# MMC_Interface.net
KiCad netlist of a schematic drawn in Altium Designer
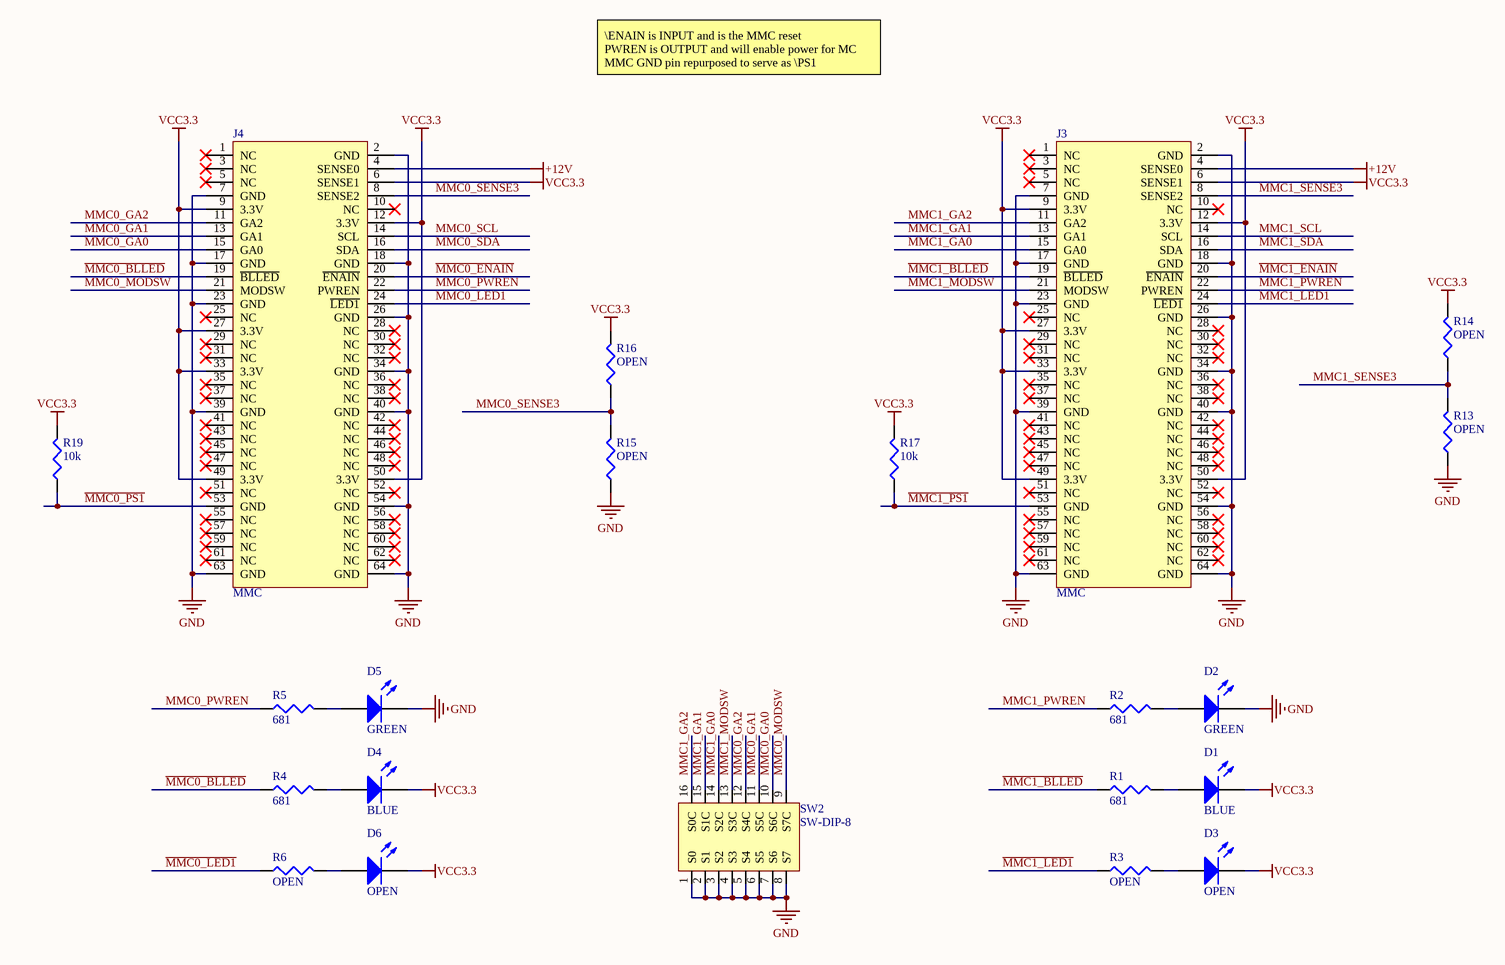
[diagram p0: MMC_Interface.SchDoc]

(export (version "E")
  (design (tool "Eeschema 10.0.6"))
  (components
    (comp (ref "D1")
      (value "BLUE")
      (footprint "LED0603_M")
      (description "Light Emitting Diode")
      (fields (field (name "MFG. PART NO.") "LTST-S270TBKT"))
      (libsource (lib "CustomSymbols") (part "LED"))
    )
    (comp (ref "D2")
      (value "GREEN")
      (footprint "LED0603_M")
      (description "Light Emitting Diode")
      (fields (field (name "MFG. PART NO.") "LTST-S270KGKT"))
      (libsource (lib "CustomSymbols") (part "LED"))
    )
    (comp (ref "D3")
      (value "OPEN")
      (footprint "LED0603_M")
      (description "Light Emitting Diode")
      (fields (field (name "MFG. PART NO.") "NA"))
      (libsource (lib "CustomSymbols") (part "LED"))
    )
    (comp (ref "D4")
      (value "BLUE")
      (footprint "LED0603_M")
      (description "Light Emitting Diode")
      (fields (field (name "MFG. PART NO.") "LTST-S270TBKT"))
      (libsource (lib "CustomSymbols") (part "LED"))
    )
    (comp (ref "D5")
      (value "GREEN")
      (footprint "LED0603_M")
      (description "Light Emitting Diode")
      (fields (field (name "MFG. PART NO.") "LTST-S270KGKT"))
      (libsource (lib "CustomSymbols") (part "LED"))
    )
    (comp (ref "D6")
      (value "OPEN")
      (footprint "LED0603_M")
      (description "Light Emitting Diode")
      (fields (field (name "MFG. PART NO.") "NA"))
      (libsource (lib "CustomSymbols") (part "LED"))
    )
    (comp (ref "J3")
      (value "MMC")
      (footprint "5120527-1")
      (description "TE 5120527-1")
      (fields (field (name "MFG. PART NO.") "5120527-1"))
      (libsource (lib "CustomSymbols") (part "MMC"))
    )
    (comp (ref "J4")
      (value "MMC")
      (footprint "5120527-1")
      (description "TE 5120527-1")
      (fields (field (name "MFG. PART NO.") "5120527-1"))
      (libsource (lib "CustomSymbols") (part "MMC"))
    )
    (comp (ref "R1")
      (value "681")
      (footprint "R0603")
      (description "Resistor")
      (fields (field (name "TOLERANCE") "1%") (field (name "MFG. PART NO.") "RC0603FR-07681RL"))
      (libsource (lib "CustomSymbols") (part "Res"))
    )
    (comp (ref "R2")
      (value "681")
      (footprint "R0603")
      (description "Resistor")
      (fields (field (name "TOLERANCE") "1%") (field (name "MFG. PART NO.") "RC0603FR-07681RL"))
      (libsource (lib "CustomSymbols") (part "Res"))
    )
    (comp (ref "R3")
      (value "OPEN")
      (footprint "R0402_IPC_H")
      (description "Resistor")
      (fields (field (name "TOLERANCE") "1%") (field (name "MFG. PART NO.") "NA"))
      (libsource (lib "CustomSymbols") (part "Res"))
    )
    (comp (ref "R4")
      (value "681")
      (footprint "R0603")
      (description "Resistor")
      (fields (field (name "TOLERANCE") "1%") (field (name "MFG. PART NO.") "RC0603FR-07681RL"))
      (libsource (lib "CustomSymbols") (part "Res"))
    )
    (comp (ref "R5")
      (value "681")
      (footprint "R0603")
      (description "Resistor")
      (fields (field (name "TOLERANCE") "1%") (field (name "MFG. PART NO.") "RC0603FR-07681RL"))
      (libsource (lib "CustomSymbols") (part "Res"))
    )
    (comp (ref "R6")
      (value "OPEN")
      (footprint "R0402_IPC_H")
      (description "Resistor")
      (fields (field (name "TOLERANCE") "1%") (field (name "MFG. PART NO.") "NA"))
      (libsource (lib "CustomSymbols") (part "Res"))
    )
    (comp (ref "R13")
      (value "OPEN")
      (footprint "R0402_IPC_H")
      (description "Resistor")
      (fields (field (name "TOLERANCE") "1%") (field (name "MFG. PART NO.") "NA"))
      (libsource (lib "CustomSymbols") (part "Res"))
    )
    (comp (ref "R14")
      (value "OPEN")
      (footprint "R0402_IPC_H")
      (description "Resistor")
      (fields (field (name "TOLERANCE") "1%") (field (name "MFG. PART NO.") "NA"))
      (libsource (lib "CustomSymbols") (part "Res"))
    )
    (comp (ref "R15")
      (value "OPEN")
      (footprint "R0402_IPC_H")
      (description "Resistor")
      (fields (field (name "TOLERANCE") "1%") (field (name "MFG. PART NO.") "NA"))
      (libsource (lib "CustomSymbols") (part "Res"))
    )
    (comp (ref "R16")
      (value "OPEN")
      (footprint "R0402_IPC_H")
      (description "Resistor")
      (fields (field (name "TOLERANCE") "1%") (field (name "MFG. PART NO.") "NA"))
      (libsource (lib "CustomSymbols") (part "Res"))
    )
    (comp (ref "R17")
      (value "10k")
      (footprint "R0402_IPC_H")
      (description "Resistor")
      (fields (field (name "TOLERANCE") "5%") (field (name "MFG. PART NO.") "ERJ-2GEJ103X"))
      (libsource (lib "CustomSymbols") (part "Res"))
    )
    (comp (ref "R19")
      (value "10k")
      (footprint "R0402_IPC_H")
      (description "Resistor")
      (fields (field (name "TOLERANCE") "5%") (field (name "MFG. PART NO.") "ERJ-2GEJ103X"))
      (libsource (lib "CustomSymbols") (part "Res"))
    )
    (comp (ref "SW2")
      (value "SW-DIP-8")
      (footprint "TDA08H0")
      (description "C&K TDA08H0SB1R")
      (fields (field (name "MFG. PART NO.") "TDA08HOSB1"))
      (libsource (lib "CustomSymbols") (part "SW-DIP-8"))
    )
  )
  (nets
    (net (code "1") (name "+12V") (class "Default")
      (node (ref "J3") (pin "4") (pinfunction "SENSE0_4") (pintype "passive"))
      (node (ref "J4") (pin "4") (pinfunction "SENSE0_4") (pintype "passive"))
    )
    (net (code "2") (name "/MMC0_BLLED") (class "Default")
      (node (ref "J4") (pin "19") (pinfunction "BLLED_19") (pintype "passive"))
      (node (ref "R4") (pin "1") (pinfunction "1_1") (pintype "passive"))
    )
    (net (code "3") (name "/MMC0_ENAIN") (class "Default")
      (node (ref "J4") (pin "20") (pinfunction "ENAIN_20") (pintype "passive"))
    )
    (net (code "4") (name "/MMC0_GA0") (class "Default")
      (node (ref "J4") (pin "15") (pinfunction "GA0_15") (pintype "passive"))
      (node (ref "SW2") (pin "10") (pinfunction "S6C_10") (pintype "passive"))
    )
    (net (code "5") (name "/MMC0_GA1") (class "Default")
      (node (ref "J4") (pin "13") (pinfunction "GA1_13") (pintype "passive"))
      (node (ref "SW2") (pin "11") (pinfunction "S5C_11") (pintype "passive"))
    )
    (net (code "6") (name "/MMC0_GA2") (class "Default")
      (node (ref "J4") (pin "11") (pinfunction "GA2_11") (pintype "passive"))
      (node (ref "SW2") (pin "12") (pinfunction "S4C_12") (pintype "passive"))
    )
    (net (code "7") (name "/MMC0_LED1") (class "Default")
      (node (ref "J4") (pin "24") (pinfunction "LED1_24") (pintype "passive"))
      (node (ref "R6") (pin "1") (pinfunction "1_1") (pintype "passive"))
    )
    (net (code "8") (name "/MMC0_MODSW") (class "Default")
      (node (ref "J4") (pin "21") (pinfunction "MODSW_21") (pintype "passive"))
      (node (ref "SW2") (pin "9") (pinfunction "S7C_9") (pintype "passive"))
    )
    (net (code "9") (name "/MMC0_PS1") (class "Default")
      (node (ref "J4") (pin "53") (pinfunction "GND_53") (pintype "power_in"))
      (node (ref "R19") (pin "1") (pinfunction "1_1") (pintype "passive"))
    )
    (net (code "10") (name "/MMC0_PWREN") (class "Default")
      (node (ref "J4") (pin "22") (pinfunction "PWREN_22") (pintype "passive"))
      (node (ref "R5") (pin "1") (pinfunction "1_1") (pintype "passive"))
    )
    (net (code "11") (name "/MMC0_SCL") (class "Default")
      (node (ref "J4") (pin "14") (pinfunction "SCL_14") (pintype "passive"))
    )
    (net (code "12") (name "/MMC0_SDA") (class "Default")
      (node (ref "J4") (pin "16") (pinfunction "SDA_16") (pintype "passive"))
    )
    (net (code "13") (name "/MMC0_SENSE3") (class "Default")
      (node (ref "J4") (pin "8") (pinfunction "SENSE2_8") (pintype "passive"))
      (node (ref "R15") (pin "2") (pinfunction "2_2") (pintype "passive"))
      (node (ref "R16") (pin "1") (pinfunction "1_1") (pintype "passive"))
    )
    (net (code "14") (name "/MMC1_BLLED") (class "Default")
      (node (ref "J3") (pin "19") (pinfunction "BLLED_19") (pintype "passive"))
      (node (ref "R1") (pin "1") (pinfunction "1_1") (pintype "passive"))
    )
    (net (code "15") (name "/MMC1_ENAIN") (class "Default")
      (node (ref "J3") (pin "20") (pinfunction "ENAIN_20") (pintype "passive"))
    )
    (net (code "16") (name "/MMC1_GA0") (class "Default")
      (node (ref "J3") (pin "15") (pinfunction "GA0_15") (pintype "passive"))
      (node (ref "SW2") (pin "14") (pinfunction "S2C_14") (pintype "passive"))
    )
    (net (code "17") (name "/MMC1_GA1") (class "Default")
      (node (ref "J3") (pin "13") (pinfunction "GA1_13") (pintype "passive"))
      (node (ref "SW2") (pin "15") (pinfunction "S1C_15") (pintype "passive"))
    )
    (net (code "18") (name "/MMC1_GA2") (class "Default")
      (node (ref "J3") (pin "11") (pinfunction "GA2_11") (pintype "passive"))
      (node (ref "SW2") (pin "16") (pinfunction "S0C_16") (pintype "passive"))
    )
    (net (code "19") (name "/MMC1_LED1") (class "Default")
      (node (ref "J3") (pin "24") (pinfunction "LED1_24") (pintype "passive"))
      (node (ref "R3") (pin "1") (pinfunction "1_1") (pintype "passive"))
    )
    (net (code "20") (name "/MMC1_MODSW") (class "Default")
      (node (ref "J3") (pin "21") (pinfunction "MODSW_21") (pintype "passive"))
      (node (ref "SW2") (pin "13") (pinfunction "S3C_13") (pintype "passive"))
    )
    (net (code "21") (name "/MMC1_PS1") (class "Default")
      (node (ref "J3") (pin "53") (pinfunction "GND_53") (pintype "power_in"))
      (node (ref "R17") (pin "1") (pinfunction "1_1") (pintype "passive"))
    )
    (net (code "22") (name "/MMC1_PWREN") (class "Default")
      (node (ref "J3") (pin "22") (pinfunction "PWREN_22") (pintype "passive"))
      (node (ref "R2") (pin "1") (pinfunction "1_1") (pintype "passive"))
    )
    (net (code "23") (name "/MMC1_SCL") (class "Default")
      (node (ref "J3") (pin "14") (pinfunction "SCL_14") (pintype "passive"))
    )
    (net (code "24") (name "/MMC1_SDA") (class "Default")
      (node (ref "J3") (pin "16") (pinfunction "SDA_16") (pintype "passive"))
    )
    (net (code "25") (name "/MMC1_SENSE3") (class "Default")
      (node (ref "J3") (pin "8") (pinfunction "SENSE2_8") (pintype "passive"))
      (node (ref "R13") (pin "2") (pinfunction "2_2") (pintype "passive"))
      (node (ref "R14") (pin "1") (pinfunction "1_1") (pintype "passive"))
    )
    (net (code "26") (name "GND") (class "Default")
      (node (ref "D2") (pin "2") (pinfunction "K_2") (pintype "passive"))
      (node (ref "D5") (pin "2") (pinfunction "K_2") (pintype "passive"))
      (node (ref "J3") (pin "17") (pinfunction "GND_17") (pintype "power_in"))
      (node (ref "J3") (pin "18") (pinfunction "GND_18") (pintype "power_in"))
      (node (ref "J3") (pin "2") (pinfunction "GND_2") (pintype "power_in"))
      (node (ref "J3") (pin "23") (pinfunction "GND_23") (pintype "power_in"))
      (node (ref "J3") (pin "26") (pinfunction "GND_26") (pintype "power_in"))
      (node (ref "J3") (pin "34") (pinfunction "GND_34") (pintype "power_in"))
      (node (ref "J3") (pin "39") (pinfunction "GND_39") (pintype "power_in"))
      (node (ref "J3") (pin "40") (pinfunction "GND_40") (pintype "power_in"))
      (node (ref "J3") (pin "54") (pinfunction "GND_54") (pintype "power_in"))
      (node (ref "J3") (pin "63") (pinfunction "GND_63") (pintype "power_in"))
      (node (ref "J3") (pin "64") (pinfunction "GND_64") (pintype "power_in"))
      (node (ref "J3") (pin "7") (pinfunction "GND_7") (pintype "power_in"))
      (node (ref "J4") (pin "17") (pinfunction "GND_17") (pintype "power_in"))
      (node (ref "J4") (pin "18") (pinfunction "GND_18") (pintype "power_in"))
      (node (ref "J4") (pin "2") (pinfunction "GND_2") (pintype "power_in"))
      (node (ref "J4") (pin "23") (pinfunction "GND_23") (pintype "power_in"))
      (node (ref "J4") (pin "26") (pinfunction "GND_26") (pintype "power_in"))
      (node (ref "J4") (pin "34") (pinfunction "GND_34") (pintype "power_in"))
      (node (ref "J4") (pin "39") (pinfunction "GND_39") (pintype "power_in"))
      (node (ref "J4") (pin "40") (pinfunction "GND_40") (pintype "power_in"))
      (node (ref "J4") (pin "54") (pinfunction "GND_54") (pintype "power_in"))
      (node (ref "J4") (pin "63") (pinfunction "GND_63") (pintype "power_in"))
      (node (ref "J4") (pin "64") (pinfunction "GND_64") (pintype "power_in"))
      (node (ref "J4") (pin "7") (pinfunction "GND_7") (pintype "power_in"))
      (node (ref "R13") (pin "1") (pinfunction "1_1") (pintype "passive"))
      (node (ref "R15") (pin "1") (pinfunction "1_1") (pintype "passive"))
      (node (ref "SW2") (pin "1") (pinfunction "S0_1") (pintype "passive"))
      (node (ref "SW2") (pin "2") (pinfunction "S1_2") (pintype "passive"))
      (node (ref "SW2") (pin "3") (pinfunction "S2_3") (pintype "passive"))
      (node (ref "SW2") (pin "4") (pinfunction "S3_4") (pintype "passive"))
      (node (ref "SW2") (pin "5") (pinfunction "S4_5") (pintype "passive"))
      (node (ref "SW2") (pin "6") (pinfunction "S5_6") (pintype "passive"))
      (node (ref "SW2") (pin "7") (pinfunction "S6_7") (pintype "passive"))
      (node (ref "SW2") (pin "8") (pinfunction "S7_8") (pintype "passive"))
    )
    (net (code "27") (name "Net-(D1-A)") (class "Default")
      (node (ref "D1") (pin "1") (pinfunction "A_1") (pintype "passive"))
      (node (ref "R1") (pin "2") (pinfunction "2_2") (pintype "passive"))
    )
    (net (code "28") (name "Net-(D2-A)") (class "Default")
      (node (ref "D2") (pin "1") (pinfunction "A_1") (pintype "passive"))
      (node (ref "R2") (pin "2") (pinfunction "2_2") (pintype "passive"))
    )
    (net (code "29") (name "Net-(D3-A)") (class "Default")
      (node (ref "D3") (pin "1") (pinfunction "A_1") (pintype "passive"))
      (node (ref "R3") (pin "2") (pinfunction "2_2") (pintype "passive"))
    )
    (net (code "30") (name "Net-(D4-A)") (class "Default")
      (node (ref "D4") (pin "1") (pinfunction "A_1") (pintype "passive"))
      (node (ref "R4") (pin "2") (pinfunction "2_2") (pintype "passive"))
    )
    (net (code "31") (name "Net-(D5-A)") (class "Default")
      (node (ref "D5") (pin "1") (pinfunction "A_1") (pintype "passive"))
      (node (ref "R5") (pin "2") (pinfunction "2_2") (pintype "passive"))
    )
    (net (code "32") (name "Net-(D6-A)") (class "Default")
      (node (ref "D6") (pin "1") (pinfunction "A_1") (pintype "passive"))
      (node (ref "R6") (pin "2") (pinfunction "2_2") (pintype "passive"))
    )
    (net (code "33") (name "VCC3.3") (class "Default")
      (node (ref "D1") (pin "2") (pinfunction "K_2") (pintype "passive"))
      (node (ref "D3") (pin "2") (pinfunction "K_2") (pintype "passive"))
      (node (ref "D4") (pin "2") (pinfunction "K_2") (pintype "passive"))
      (node (ref "D6") (pin "2") (pinfunction "K_2") (pintype "passive"))
      (node (ref "J3") (pin "12") (pinfunction "3.3V_12") (pintype "power_in"))
      (node (ref "J3") (pin "27") (pinfunction "3.3V_27") (pintype "power_in"))
      (node (ref "J3") (pin "33") (pinfunction "3.3V_33") (pintype "power_in"))
      (node (ref "J3") (pin "49") (pinfunction "3.3V_49") (pintype "power_in"))
      (node (ref "J3") (pin "50") (pinfunction "3.3V_50") (pintype "power_in"))
      (node (ref "J3") (pin "6") (pinfunction "SENSE1_6") (pintype "passive"))
      (node (ref "J3") (pin "9") (pinfunction "3.3V_9") (pintype "power_in"))
      (node (ref "J4") (pin "12") (pinfunction "3.3V_12") (pintype "power_in"))
      (node (ref "J4") (pin "27") (pinfunction "3.3V_27") (pintype "power_in"))
      (node (ref "J4") (pin "33") (pinfunction "3.3V_33") (pintype "power_in"))
      (node (ref "J4") (pin "49") (pinfunction "3.3V_49") (pintype "power_in"))
      (node (ref "J4") (pin "50") (pinfunction "3.3V_50") (pintype "power_in"))
      (node (ref "J4") (pin "6") (pinfunction "SENSE1_6") (pintype "passive"))
      (node (ref "J4") (pin "9") (pinfunction "3.3V_9") (pintype "power_in"))
      (node (ref "R14") (pin "2") (pinfunction "2_2") (pintype "passive"))
      (node (ref "R16") (pin "2") (pinfunction "2_2") (pintype "passive"))
      (node (ref "R17") (pin "2") (pinfunction "2_2") (pintype "passive"))
      (node (ref "R19") (pin "2") (pinfunction "2_2") (pintype "passive"))
    )
    (net (code "34") (name "unconnected-(J3-NC-Pad1)") (class "Default")
      (node (ref "J3") (pin "1") (pinfunction "NC_1") (pintype "passive+no_connect"))
    )
    (net (code "35") (name "unconnected-(J3-NC-Pad3)") (class "Default")
      (node (ref "J3") (pin "3") (pinfunction "NC_3") (pintype "passive+no_connect"))
    )
    (net (code "36") (name "unconnected-(J3-NC-Pad5)") (class "Default")
      (node (ref "J3") (pin "5") (pinfunction "NC_5") (pintype "passive+no_connect"))
    )
    (net (code "37") (name "unconnected-(J3-NC-Pad10)") (class "Default")
      (node (ref "J3") (pin "10") (pinfunction "NC_10") (pintype "passive+no_connect"))
    )
    (net (code "38") (name "unconnected-(J3-NC-Pad25)") (class "Default")
      (node (ref "J3") (pin "25") (pinfunction "NC_25") (pintype "passive+no_connect"))
    )
    (net (code "39") (name "unconnected-(J3-NC-Pad28)") (class "Default")
      (node (ref "J3") (pin "28") (pinfunction "NC_28") (pintype "passive+no_connect"))
    )
    (net (code "40") (name "unconnected-(J3-NC-Pad29)") (class "Default")
      (node (ref "J3") (pin "29") (pinfunction "NC_29") (pintype "passive+no_connect"))
    )
    (net (code "41") (name "unconnected-(J3-NC-Pad30)") (class "Default")
      (node (ref "J3") (pin "30") (pinfunction "NC_30") (pintype "passive+no_connect"))
    )
    (net (code "42") (name "unconnected-(J3-NC-Pad31)") (class "Default")
      (node (ref "J3") (pin "31") (pinfunction "NC_31") (pintype "passive+no_connect"))
    )
    (net (code "43") (name "unconnected-(J3-NC-Pad32)") (class "Default")
      (node (ref "J3") (pin "32") (pinfunction "NC_32") (pintype "passive+no_connect"))
    )
    (net (code "44") (name "unconnected-(J3-NC-Pad35)") (class "Default")
      (node (ref "J3") (pin "35") (pinfunction "NC_35") (pintype "passive+no_connect"))
    )
    (net (code "45") (name "unconnected-(J3-NC-Pad36)") (class "Default")
      (node (ref "J3") (pin "36") (pinfunction "NC_36") (pintype "passive+no_connect"))
    )
    (net (code "46") (name "unconnected-(J3-NC-Pad37)") (class "Default")
      (node (ref "J3") (pin "37") (pinfunction "NC_37") (pintype "passive+no_connect"))
    )
    (net (code "47") (name "unconnected-(J3-NC-Pad38)") (class "Default")
      (node (ref "J3") (pin "38") (pinfunction "NC_38") (pintype "passive+no_connect"))
    )
    (net (code "48") (name "unconnected-(J3-NC-Pad41)") (class "Default")
      (node (ref "J3") (pin "41") (pinfunction "NC_41") (pintype "passive+no_connect"))
    )
    (net (code "49") (name "unconnected-(J3-NC-Pad42)") (class "Default")
      (node (ref "J3") (pin "42") (pinfunction "NC_42") (pintype "passive+no_connect"))
    )
    (net (code "50") (name "unconnected-(J3-NC-Pad43)") (class "Default")
      (node (ref "J3") (pin "43") (pinfunction "NC_43") (pintype "passive+no_connect"))
    )
    (net (code "51") (name "unconnected-(J3-NC-Pad44)") (class "Default")
      (node (ref "J3") (pin "44") (pinfunction "NC_44") (pintype "passive+no_connect"))
    )
    (net (code "52") (name "unconnected-(J3-NC-Pad45)") (class "Default")
      (node (ref "J3") (pin "45") (pinfunction "NC_45") (pintype "passive+no_connect"))
    )
    (net (code "53") (name "unconnected-(J3-NC-Pad46)") (class "Default")
      (node (ref "J3") (pin "46") (pinfunction "NC_46") (pintype "passive+no_connect"))
    )
    (net (code "54") (name "unconnected-(J3-NC-Pad47)") (class "Default")
      (node (ref "J3") (pin "47") (pinfunction "NC_47") (pintype "passive+no_connect"))
    )
    (net (code "55") (name "unconnected-(J3-NC-Pad48)") (class "Default")
      (node (ref "J3") (pin "48") (pinfunction "NC_48") (pintype "passive+no_connect"))
    )
    (net (code "56") (name "unconnected-(J3-NC-Pad51)") (class "Default")
      (node (ref "J3") (pin "51") (pinfunction "NC_51") (pintype "passive+no_connect"))
    )
    (net (code "57") (name "unconnected-(J3-NC-Pad52)") (class "Default")
      (node (ref "J3") (pin "52") (pinfunction "NC_52") (pintype "passive+no_connect"))
    )
    (net (code "58") (name "unconnected-(J3-NC-Pad55)") (class "Default")
      (node (ref "J3") (pin "55") (pinfunction "NC_55") (pintype "passive+no_connect"))
    )
    (net (code "59") (name "unconnected-(J3-NC-Pad56)") (class "Default")
      (node (ref "J3") (pin "56") (pinfunction "NC_56") (pintype "passive+no_connect"))
    )
    (net (code "60") (name "unconnected-(J3-NC-Pad57)") (class "Default")
      (node (ref "J3") (pin "57") (pinfunction "NC_57") (pintype "passive+no_connect"))
    )
    (net (code "61") (name "unconnected-(J3-NC-Pad58)") (class "Default")
      (node (ref "J3") (pin "58") (pinfunction "NC_58") (pintype "passive+no_connect"))
    )
    (net (code "62") (name "unconnected-(J3-NC-Pad59)") (class "Default")
      (node (ref "J3") (pin "59") (pinfunction "NC_59") (pintype "passive+no_connect"))
    )
    (net (code "63") (name "unconnected-(J3-NC-Pad60)") (class "Default")
      (node (ref "J3") (pin "60") (pinfunction "NC_60") (pintype "passive+no_connect"))
    )
    (net (code "64") (name "unconnected-(J3-NC-Pad61)") (class "Default")
      (node (ref "J3") (pin "61") (pinfunction "NC_61") (pintype "passive+no_connect"))
    )
    (net (code "65") (name "unconnected-(J3-NC-Pad62)") (class "Default")
      (node (ref "J3") (pin "62") (pinfunction "NC_62") (pintype "passive+no_connect"))
    )
    (net (code "66") (name "unconnected-(J4-NC-Pad1)") (class "Default")
      (node (ref "J4") (pin "1") (pinfunction "NC_1") (pintype "passive+no_connect"))
    )
    (net (code "67") (name "unconnected-(J4-NC-Pad3)") (class "Default")
      (node (ref "J4") (pin "3") (pinfunction "NC_3") (pintype "passive+no_connect"))
    )
    (net (code "68") (name "unconnected-(J4-NC-Pad5)") (class "Default")
      (node (ref "J4") (pin "5") (pinfunction "NC_5") (pintype "passive+no_connect"))
    )
    (net (code "69") (name "unconnected-(J4-NC-Pad10)") (class "Default")
      (node (ref "J4") (pin "10") (pinfunction "NC_10") (pintype "passive+no_connect"))
    )
    (net (code "70") (name "unconnected-(J4-NC-Pad25)") (class "Default")
      (node (ref "J4") (pin "25") (pinfunction "NC_25") (pintype "passive+no_connect"))
    )
    (net (code "71") (name "unconnected-(J4-NC-Pad28)") (class "Default")
      (node (ref "J4") (pin "28") (pinfunction "NC_28") (pintype "passive+no_connect"))
    )
    (net (code "72") (name "unconnected-(J4-NC-Pad29)") (class "Default")
      (node (ref "J4") (pin "29") (pinfunction "NC_29") (pintype "passive+no_connect"))
    )
    (net (code "73") (name "unconnected-(J4-NC-Pad30)") (class "Default")
      (node (ref "J4") (pin "30") (pinfunction "NC_30") (pintype "passive+no_connect"))
    )
    (net (code "74") (name "unconnected-(J4-NC-Pad31)") (class "Default")
      (node (ref "J4") (pin "31") (pinfunction "NC_31") (pintype "passive+no_connect"))
    )
    (net (code "75") (name "unconnected-(J4-NC-Pad32)") (class "Default")
      (node (ref "J4") (pin "32") (pinfunction "NC_32") (pintype "passive+no_connect"))
    )
    (net (code "76") (name "unconnected-(J4-NC-Pad35)") (class "Default")
      (node (ref "J4") (pin "35") (pinfunction "NC_35") (pintype "passive+no_connect"))
    )
    (net (code "77") (name "unconnected-(J4-NC-Pad36)") (class "Default")
      (node (ref "J4") (pin "36") (pinfunction "NC_36") (pintype "passive+no_connect"))
    )
    (net (code "78") (name "unconnected-(J4-NC-Pad37)") (class "Default")
      (node (ref "J4") (pin "37") (pinfunction "NC_37") (pintype "passive+no_connect"))
    )
    (net (code "79") (name "unconnected-(J4-NC-Pad38)") (class "Default")
      (node (ref "J4") (pin "38") (pinfunction "NC_38") (pintype "passive+no_connect"))
    )
    (net (code "80") (name "unconnected-(J4-NC-Pad41)") (class "Default")
      (node (ref "J4") (pin "41") (pinfunction "NC_41") (pintype "passive+no_connect"))
    )
    (net (code "81") (name "unconnected-(J4-NC-Pad42)") (class "Default")
      (node (ref "J4") (pin "42") (pinfunction "NC_42") (pintype "passive+no_connect"))
    )
    (net (code "82") (name "unconnected-(J4-NC-Pad43)") (class "Default")
      (node (ref "J4") (pin "43") (pinfunction "NC_43") (pintype "passive+no_connect"))
    )
    (net (code "83") (name "unconnected-(J4-NC-Pad44)") (class "Default")
      (node (ref "J4") (pin "44") (pinfunction "NC_44") (pintype "passive+no_connect"))
    )
    (net (code "84") (name "unconnected-(J4-NC-Pad45)") (class "Default")
      (node (ref "J4") (pin "45") (pinfunction "NC_45") (pintype "passive+no_connect"))
    )
    (net (code "85") (name "unconnected-(J4-NC-Pad46)") (class "Default")
      (node (ref "J4") (pin "46") (pinfunction "NC_46") (pintype "passive+no_connect"))
    )
    (net (code "86") (name "unconnected-(J4-NC-Pad47)") (class "Default")
      (node (ref "J4") (pin "47") (pinfunction "NC_47") (pintype "passive+no_connect"))
    )
    (net (code "87") (name "unconnected-(J4-NC-Pad48)") (class "Default")
      (node (ref "J4") (pin "48") (pinfunction "NC_48") (pintype "passive+no_connect"))
    )
    (net (code "88") (name "unconnected-(J4-NC-Pad51)") (class "Default")
      (node (ref "J4") (pin "51") (pinfunction "NC_51") (pintype "passive+no_connect"))
    )
    (net (code "89") (name "unconnected-(J4-NC-Pad52)") (class "Default")
      (node (ref "J4") (pin "52") (pinfunction "NC_52") (pintype "passive+no_connect"))
    )
    (net (code "90") (name "unconnected-(J4-NC-Pad55)") (class "Default")
      (node (ref "J4") (pin "55") (pinfunction "NC_55") (pintype "passive+no_connect"))
    )
    (net (code "91") (name "unconnected-(J4-NC-Pad56)") (class "Default")
      (node (ref "J4") (pin "56") (pinfunction "NC_56") (pintype "passive+no_connect"))
    )
    (net (code "92") (name "unconnected-(J4-NC-Pad57)") (class "Default")
      (node (ref "J4") (pin "57") (pinfunction "NC_57") (pintype "passive+no_connect"))
    )
    (net (code "93") (name "unconnected-(J4-NC-Pad58)") (class "Default")
      (node (ref "J4") (pin "58") (pinfunction "NC_58") (pintype "passive+no_connect"))
    )
    (net (code "94") (name "unconnected-(J4-NC-Pad59)") (class "Default")
      (node (ref "J4") (pin "59") (pinfunction "NC_59") (pintype "passive+no_connect"))
    )
    (net (code "95") (name "unconnected-(J4-NC-Pad60)") (class "Default")
      (node (ref "J4") (pin "60") (pinfunction "NC_60") (pintype "passive+no_connect"))
    )
    (net (code "96") (name "unconnected-(J4-NC-Pad61)") (class "Default")
      (node (ref "J4") (pin "61") (pinfunction "NC_61") (pintype "passive+no_connect"))
    )
    (net (code "97") (name "unconnected-(J4-NC-Pad62)") (class "Default")
      (node (ref "J4") (pin "62") (pinfunction "NC_62") (pintype "passive+no_connect"))
    )
  )
)
